# raspi3_hat_v1.net
KiCad netlist of a schematic drawn in EAGLE
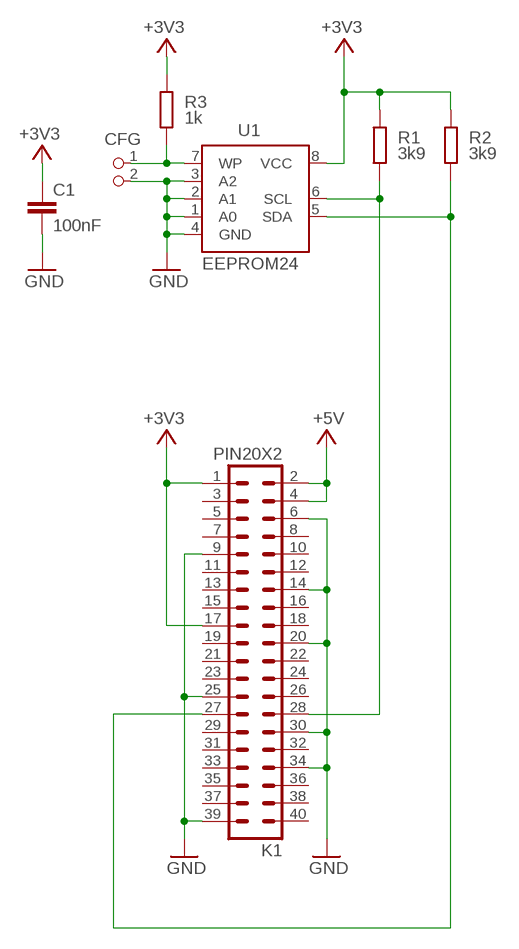
[diagram p0: schematic, sheet 1]

(export (version "E")
  (design (tool "Eeschema 10.0.6"))
  (components
    (comp (ref "C1")
      (value "100nF")
      (footprint "eagle-import:C0805K")
      (libsource (lib "eagle-import") (part "C-EUC0805K"))
    )
    (comp (ref "CFG")
      (value "PIN2_100")
      (footprint "eagle-import:PIN_W_2")
      (libsource (lib "eagle-import") (part "PIN2_100"))
    )
    (comp (ref "K1")
      (value "PIN20X2")
      (footprint "eagle-import:PIN_20X2")
      (libsource (lib "eagle-import") (part "PIN20X2"))
    )
    (comp (ref "R1")
      (value "3k9")
      (footprint "eagle-import:M0805")
      (fields (field (name "TOLERANCE") "5%"))
      (libsource (lib "eagle-import") (part "R-EU_M0805"))
    )
    (comp (ref "R2")
      (value "3k9")
      (footprint "eagle-import:M0805")
      (fields (field (name "TOLERANCE") "5%"))
      (libsource (lib "eagle-import") (part "R-EU_M0805"))
    )
    (comp (ref "R3")
      (value "1k")
      (footprint "eagle-import:M0805")
      (fields (field (name "TOLERANCE") "5%"))
      (libsource (lib "eagle-import") (part "R-EU_M0805"))
    )
    (comp (ref "U1")
      (value "EEPROM24")
      (footprint "eagle-import:SOIC8")
      (libsource (lib "eagle-import") (part "EEPROM24"))
    )
  )
  (nets
    (net (code "1") (name "+3V3") (class "Default")
      (node (ref "C1") (pin "1") (pinfunction "1_1") (pintype "passive"))
      (node (ref "K1") (pin "1") (pinfunction "1_1") (pintype "passive"))
      (node (ref "K1") (pin "17") (pinfunction "17_17") (pintype "passive"))
      (node (ref "R1") (pin "2") (pinfunction "2_2") (pintype "passive"))
      (node (ref "R2") (pin "2") (pinfunction "2_2") (pintype "passive"))
      (node (ref "R3") (pin "2") (pinfunction "2_2") (pintype "passive"))
      (node (ref "U1") (pin "8") (pinfunction "VCC_8") (pintype "power_in"))
    )
    (net (code "2") (name "+5V") (class "Default")
      (node (ref "K1") (pin "2") (pinfunction "2_2") (pintype "passive"))
      (node (ref "K1") (pin "4") (pinfunction "4_4") (pintype "passive"))
    )
    (net (code "3") (name "GND") (class "Default")
      (node (ref "C1") (pin "2") (pinfunction "2_2") (pintype "passive"))
      (node (ref "CFG") (pin "2") (pinfunction "2_2") (pintype "passive"))
      (node (ref "K1") (pin "14") (pinfunction "14_14") (pintype "passive"))
      (node (ref "K1") (pin "20") (pinfunction "20_20") (pintype "passive"))
      (node (ref "K1") (pin "25") (pinfunction "25_25") (pintype "passive"))
      (node (ref "K1") (pin "30") (pinfunction "30_30") (pintype "passive"))
      (node (ref "K1") (pin "34") (pinfunction "34_34") (pintype "passive"))
      (node (ref "K1") (pin "39") (pinfunction "39_39") (pintype "passive"))
      (node (ref "K1") (pin "6") (pinfunction "6_6") (pintype "passive"))
      (node (ref "K1") (pin "9") (pinfunction "9_9") (pintype "passive"))
      (node (ref "U1") (pin "1") (pinfunction "A0_1") (pintype "input"))
      (node (ref "U1") (pin "2") (pinfunction "A1_2") (pintype "input"))
      (node (ref "U1") (pin "3") (pinfunction "A2_3") (pintype "input"))
      (node (ref "U1") (pin "4") (pinfunction "GND_4") (pintype "power_in"))
    )
    (net (code "4") (name "Net-(U1-SCL)") (class "Default")
      (node (ref "K1") (pin "28") (pinfunction "28_28") (pintype "passive"))
      (node (ref "R1") (pin "1") (pinfunction "1_1") (pintype "passive"))
      (node (ref "U1") (pin "6") (pinfunction "SCL_6") (pintype "input"))
    )
    (net (code "5") (name "Net-(U1-SDA)") (class "Default")
      (node (ref "K1") (pin "27") (pinfunction "27_27") (pintype "passive"))
      (node (ref "R2") (pin "1") (pinfunction "1_1") (pintype "passive"))
      (node (ref "U1") (pin "5") (pinfunction "SDA_5") (pintype "bidirectional"))
    )
    (net (code "6") (name "Net-(U1-WP)") (class "Default")
      (node (ref "CFG") (pin "1") (pinfunction "1_1") (pintype "passive"))
      (node (ref "R3") (pin "1") (pinfunction "1_1") (pintype "passive"))
      (node (ref "U1") (pin "7") (pinfunction "WP_7") (pintype "input"))
    )
    (net (code "7") (name "unconnected-(K1-Pad3)") (class "Default")
      (node (ref "K1") (pin "3") (pinfunction "3_3") (pintype "passive"))
    )
    (net (code "8") (name "unconnected-(K1-Pad5)") (class "Default")
      (node (ref "K1") (pin "5") (pinfunction "5_5") (pintype "passive"))
    )
    (net (code "9") (name "unconnected-(K1-Pad7)") (class "Default")
      (node (ref "K1") (pin "7") (pinfunction "7_7") (pintype "passive"))
    )
    (net (code "10") (name "unconnected-(K1-Pad8)") (class "Default")
      (node (ref "K1") (pin "8") (pinfunction "8_8") (pintype "passive"))
    )
    (net (code "11") (name "unconnected-(K1-Pad10)") (class "Default")
      (node (ref "K1") (pin "10") (pinfunction "10_10") (pintype "passive"))
    )
    (net (code "12") (name "unconnected-(K1-Pad11)") (class "Default")
      (node (ref "K1") (pin "11") (pinfunction "11_11") (pintype "passive"))
    )
    (net (code "13") (name "unconnected-(K1-Pad12)") (class "Default")
      (node (ref "K1") (pin "12") (pinfunction "12_12") (pintype "passive"))
    )
    (net (code "14") (name "unconnected-(K1-Pad13)") (class "Default")
      (node (ref "K1") (pin "13") (pinfunction "13_13") (pintype "passive"))
    )
    (net (code "15") (name "unconnected-(K1-Pad15)") (class "Default")
      (node (ref "K1") (pin "15") (pinfunction "15_15") (pintype "passive"))
    )
    (net (code "16") (name "unconnected-(K1-Pad16)") (class "Default")
      (node (ref "K1") (pin "16") (pinfunction "16_16") (pintype "passive"))
    )
    (net (code "17") (name "unconnected-(K1-Pad18)") (class "Default")
      (node (ref "K1") (pin "18") (pinfunction "18_18") (pintype "passive"))
    )
    (net (code "18") (name "unconnected-(K1-Pad19)") (class "Default")
      (node (ref "K1") (pin "19") (pinfunction "19_19") (pintype "passive"))
    )
    (net (code "19") (name "unconnected-(K1-Pad21)") (class "Default")
      (node (ref "K1") (pin "21") (pinfunction "21_21") (pintype "passive"))
    )
    (net (code "20") (name "unconnected-(K1-Pad22)") (class "Default")
      (node (ref "K1") (pin "22") (pinfunction "22_22") (pintype "passive"))
    )
    (net (code "21") (name "unconnected-(K1-Pad23)") (class "Default")
      (node (ref "K1") (pin "23") (pinfunction "23_23") (pintype "passive"))
    )
    (net (code "22") (name "unconnected-(K1-Pad24)") (class "Default")
      (node (ref "K1") (pin "24") (pinfunction "24_24") (pintype "passive"))
    )
    (net (code "23") (name "unconnected-(K1-Pad26)") (class "Default")
      (node (ref "K1") (pin "26") (pinfunction "26_26") (pintype "passive"))
    )
    (net (code "24") (name "unconnected-(K1-Pad29)") (class "Default")
      (node (ref "K1") (pin "29") (pinfunction "29_29") (pintype "passive"))
    )
    (net (code "25") (name "unconnected-(K1-Pad31)") (class "Default")
      (node (ref "K1") (pin "31") (pinfunction "31_31") (pintype "passive"))
    )
    (net (code "26") (name "unconnected-(K1-Pad32)") (class "Default")
      (node (ref "K1") (pin "32") (pinfunction "32_32") (pintype "passive"))
    )
    (net (code "27") (name "unconnected-(K1-Pad33)") (class "Default")
      (node (ref "K1") (pin "33") (pinfunction "33_33") (pintype "passive"))
    )
    (net (code "28") (name "unconnected-(K1-Pad35)") (class "Default")
      (node (ref "K1") (pin "35") (pinfunction "35_35") (pintype "passive"))
    )
    (net (code "29") (name "unconnected-(K1-Pad36)") (class "Default")
      (node (ref "K1") (pin "36") (pinfunction "36_36") (pintype "passive"))
    )
    (net (code "30") (name "unconnected-(K1-Pad37)") (class "Default")
      (node (ref "K1") (pin "37") (pinfunction "37_37") (pintype "passive"))
    )
    (net (code "31") (name "unconnected-(K1-Pad38)") (class "Default")
      (node (ref "K1") (pin "38") (pinfunction "38_38") (pintype "passive"))
    )
    (net (code "32") (name "unconnected-(K1-Pad40)") (class "Default")
      (node (ref "K1") (pin "40") (pinfunction "40_40") (pintype "passive"))
    )
  )
)
